# LQFP-QFN-44_Test.net
KiCad netlist of a schematic drawn in EAGLE
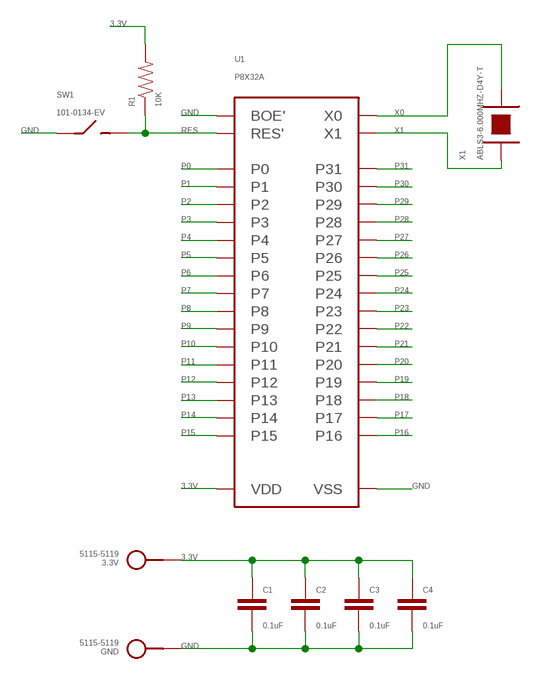
[diagram p0: schematic, sheet 1]

(export (version "E")
  (design (tool "Eeschema 10.0.6"))
  (components
    (comp (ref "3.3V")
      (value "5115-5119")
      (footprint "eagle-import:KEYSTONE_5115-5119")
      (libsource (lib "eagle-import") (part "TEST_POINT_SINGLEKEYSTONE_5115-5119"))
    )
    (comp (ref "C1")
      (value "0.1uF")
      (footprint "eagle-import:0402")
      (libsource (lib "eagle-import") (part "CAPACITOR_NON_POLAR0402"))
    )
    (comp (ref "C2")
      (value "0.1uF")
      (footprint "eagle-import:0402")
      (libsource (lib "eagle-import") (part "CAPACITOR_NON_POLAR0402"))
    )
    (comp (ref "C3")
      (value "0.1uF")
      (footprint "eagle-import:0402")
      (libsource (lib "eagle-import") (part "CAPACITOR_NON_POLAR0402"))
    )
    (comp (ref "C4")
      (value "0.1uF")
      (footprint "eagle-import:0402")
      (libsource (lib "eagle-import") (part "CAPACITOR_NON_POLAR0402"))
    )
    (comp (ref "GND")
      (value "5115-5119")
      (footprint "eagle-import:KEYSTONE_5115-5119")
      (libsource (lib "eagle-import") (part "TEST_POINT_SINGLEKEYSTONE_5115-5119"))
    )
    (comp (ref "R1")
      (value "10K")
      (footprint "eagle-import:0402")
      (libsource (lib "eagle-import") (part "RESISTOR0402"))
    )
    (comp (ref "SW1")
      (value "101-0134-EV")
      (footprint "eagle-import:101-0134-EV")
      (libsource (lib "eagle-import") (part "SPST101-0134-EV"))
    )
    (comp (ref "U1")
      (value "P8X32A")
      (footprint "eagle-import:DUAL_LQFP_QFN_44")
      (libsource (lib "eagle-import") (part "P8X32A_PROPELLERLQFP/QFN-44"))
    )
    (comp (ref "X1")
      (value "ABLS3-6.000MHZ-D4Y-T")
      (footprint "eagle-import:HC-49_US_SM")
      (libsource (lib "eagle-import") (part "CRYSTALHC-49"))
    )
  )
  (nets
    (net (code "1") (name "/3.3V") (class "Default")
      (node (ref "3.3V") (pin "P$1") (pinfunction "P$1_P$1") (pintype "bidirectional"))
      (node (ref "C1") (pin "1") (pinfunction "1_1") (pintype "passive"))
      (node (ref "C2") (pin "1") (pinfunction "1_1") (pintype "passive"))
      (node (ref "C3") (pin "1") (pinfunction "1_1") (pintype "passive"))
      (node (ref "C4") (pin "1") (pinfunction "1_1") (pintype "passive"))
      (node (ref "R1") (pin "2") (pinfunction "2_2") (pintype "passive"))
      (node (ref "U1") (pin "18") (pinfunction "VDD_18") (pintype "bidirectional"))
      (node (ref "U1") (pin "30") (pinfunction "VDD_30") (pintype "bidirectional"))
      (node (ref "U1") (pin "40") (pinfunction "VDD_40") (pintype "bidirectional"))
      (node (ref "U1") (pin "52") (pinfunction "VDD_52") (pintype "bidirectional"))
      (node (ref "U1") (pin "62") (pinfunction "VDD_62") (pintype "bidirectional"))
      (node (ref "U1") (pin "74") (pinfunction "VDD_74") (pintype "bidirectional"))
      (node (ref "U1") (pin "8") (pinfunction "VDD_8") (pintype "bidirectional"))
      (node (ref "U1") (pin "84") (pinfunction "VDD_84") (pintype "bidirectional"))
    )
    (net (code "2") (name "/GND") (class "Default")
      (node (ref "C1") (pin "2") (pinfunction "2_2") (pintype "passive"))
      (node (ref "C2") (pin "2") (pinfunction "2_2") (pintype "passive"))
      (node (ref "C3") (pin "2") (pinfunction "2_2") (pintype "passive"))
      (node (ref "C4") (pin "2") (pinfunction "2_2") (pintype "passive"))
      (node (ref "GND") (pin "P$1") (pinfunction "P$1_P$1") (pintype "bidirectional"))
      (node (ref "SW1") (pin "1") (pinfunction "A_1") (pintype "bidirectional"))
      (node (ref "U1") (pin "17") (pinfunction "VSS_17") (pintype "bidirectional"))
      (node (ref "U1") (pin "27") (pinfunction "VSS_27") (pintype "bidirectional"))
      (node (ref "U1") (pin "39") (pinfunction "VSS_39") (pintype "bidirectional"))
      (node (ref "U1") (pin "49") (pinfunction "VSS_49") (pintype "bidirectional"))
      (node (ref "U1") (pin "5") (pinfunction "VSS_5") (pintype "bidirectional"))
      (node (ref "U1") (pin "50") (pinfunction "BOE'_50") (pintype "bidirectional"))
      (node (ref "U1") (pin "6") (pinfunction "BOE'_6") (pintype "bidirectional"))
      (node (ref "U1") (pin "61") (pinfunction "VSS_61") (pintype "bidirectional"))
      (node (ref "U1") (pin "71") (pinfunction "VSS_71") (pintype "bidirectional"))
      (node (ref "U1") (pin "83") (pinfunction "VSS_83") (pintype "bidirectional"))
      (node (ref "U1") (pin "PAD") (pinfunction "VSS_PAD") (pintype "bidirectional"))
    )
    (net (code "3") (name "/P0") (class "Default")
      (node (ref "U1") (pin "41") (pinfunction "P0_41") (pintype "bidirectional"))
      (node (ref "U1") (pin "85") (pinfunction "P0_85") (pintype "bidirectional"))
    )
    (net (code "4") (name "/P1") (class "Default")
      (node (ref "U1") (pin "42") (pinfunction "P1_42") (pintype "bidirectional"))
      (node (ref "U1") (pin "86") (pinfunction "P1_86") (pintype "bidirectional"))
    )
    (net (code "5") (name "/P2") (class "Default")
      (node (ref "U1") (pin "43") (pinfunction "P2_43") (pintype "bidirectional"))
      (node (ref "U1") (pin "87") (pinfunction "P2_87") (pintype "bidirectional"))
    )
    (net (code "6") (name "/P3") (class "Default")
      (node (ref "U1") (pin "44") (pinfunction "P3_44") (pintype "bidirectional"))
      (node (ref "U1") (pin "88") (pinfunction "P3_88") (pintype "bidirectional"))
    )
    (net (code "7") (name "/P4") (class "Default")
      (node (ref "U1") (pin "1") (pinfunction "P4_1") (pintype "bidirectional"))
      (node (ref "U1") (pin "45") (pinfunction "P4_45") (pintype "bidirectional"))
    )
    (net (code "8") (name "/P5") (class "Default")
      (node (ref "U1") (pin "2") (pinfunction "P5_2") (pintype "bidirectional"))
      (node (ref "U1") (pin "46") (pinfunction "P5_46") (pintype "bidirectional"))
    )
    (net (code "9") (name "/P6") (class "Default")
      (node (ref "U1") (pin "3") (pinfunction "P6_3") (pintype "bidirectional"))
      (node (ref "U1") (pin "47") (pinfunction "P6_47") (pintype "bidirectional"))
    )
    (net (code "10") (name "/P7") (class "Default")
      (node (ref "U1") (pin "4") (pinfunction "P7_4") (pintype "bidirectional"))
      (node (ref "U1") (pin "48") (pinfunction "P7_48") (pintype "bidirectional"))
    )
    (net (code "11") (name "/P8") (class "Default")
      (node (ref "U1") (pin "53") (pinfunction "P8_53") (pintype "bidirectional"))
      (node (ref "U1") (pin "9") (pinfunction "P8_9") (pintype "bidirectional"))
    )
    (net (code "12") (name "/P9") (class "Default")
      (node (ref "U1") (pin "10") (pinfunction "P9_10") (pintype "bidirectional"))
      (node (ref "U1") (pin "54") (pinfunction "P9_54") (pintype "bidirectional"))
    )
    (net (code "13") (name "/P10") (class "Default")
      (node (ref "U1") (pin "11") (pinfunction "P10_11") (pintype "bidirectional"))
      (node (ref "U1") (pin "55") (pinfunction "P10_55") (pintype "bidirectional"))
    )
    (net (code "14") (name "/P11") (class "Default")
      (node (ref "U1") (pin "12") (pinfunction "P11_12") (pintype "bidirectional"))
      (node (ref "U1") (pin "56") (pinfunction "P11_56") (pintype "bidirectional"))
    )
    (net (code "15") (name "/P12") (class "Default")
      (node (ref "U1") (pin "13") (pinfunction "P12_13") (pintype "bidirectional"))
      (node (ref "U1") (pin "57") (pinfunction "P12_57") (pintype "bidirectional"))
    )
    (net (code "16") (name "/P13") (class "Default")
      (node (ref "U1") (pin "14") (pinfunction "P13_14") (pintype "bidirectional"))
      (node (ref "U1") (pin "58") (pinfunction "P13_58") (pintype "bidirectional"))
    )
    (net (code "17") (name "/P14") (class "Default")
      (node (ref "U1") (pin "15") (pinfunction "P14_15") (pintype "bidirectional"))
      (node (ref "U1") (pin "59") (pinfunction "P14_59") (pintype "bidirectional"))
    )
    (net (code "18") (name "/P15") (class "Default")
      (node (ref "U1") (pin "16") (pinfunction "P15_16") (pintype "bidirectional"))
      (node (ref "U1") (pin "60") (pinfunction "P15_60") (pintype "bidirectional"))
    )
    (net (code "19") (name "/P16") (class "Default")
      (node (ref "U1") (pin "19") (pinfunction "P16_19") (pintype "bidirectional"))
      (node (ref "U1") (pin "63") (pinfunction "P16_63") (pintype "bidirectional"))
    )
    (net (code "20") (name "/P17") (class "Default")
      (node (ref "U1") (pin "20") (pinfunction "P17_20") (pintype "bidirectional"))
      (node (ref "U1") (pin "64") (pinfunction "P17_64") (pintype "bidirectional"))
    )
    (net (code "21") (name "/P18") (class "Default")
      (node (ref "U1") (pin "21") (pinfunction "P18_21") (pintype "bidirectional"))
      (node (ref "U1") (pin "65") (pinfunction "P18_65") (pintype "bidirectional"))
    )
    (net (code "22") (name "/P19") (class "Default")
      (node (ref "U1") (pin "22") (pinfunction "P19_22") (pintype "bidirectional"))
      (node (ref "U1") (pin "66") (pinfunction "P19_66") (pintype "bidirectional"))
    )
    (net (code "23") (name "/P20") (class "Default")
      (node (ref "U1") (pin "23") (pinfunction "P20_23") (pintype "bidirectional"))
      (node (ref "U1") (pin "67") (pinfunction "P20_67") (pintype "bidirectional"))
    )
    (net (code "24") (name "/P21") (class "Default")
      (node (ref "U1") (pin "24") (pinfunction "P21_24") (pintype "bidirectional"))
      (node (ref "U1") (pin "68") (pinfunction "P21_68") (pintype "bidirectional"))
    )
    (net (code "25") (name "/P22") (class "Default")
      (node (ref "U1") (pin "25") (pinfunction "P22_25") (pintype "bidirectional"))
      (node (ref "U1") (pin "69") (pinfunction "P22_69") (pintype "bidirectional"))
    )
    (net (code "26") (name "/P23") (class "Default")
      (node (ref "U1") (pin "26") (pinfunction "P23_26") (pintype "bidirectional"))
      (node (ref "U1") (pin "70") (pinfunction "P23_70") (pintype "bidirectional"))
    )
    (net (code "27") (name "/P24") (class "Default")
      (node (ref "U1") (pin "31") (pinfunction "P24_31") (pintype "bidirectional"))
      (node (ref "U1") (pin "75") (pinfunction "P24_75") (pintype "bidirectional"))
    )
    (net (code "28") (name "/P25") (class "Default")
      (node (ref "U1") (pin "32") (pinfunction "P25_32") (pintype "bidirectional"))
      (node (ref "U1") (pin "76") (pinfunction "P25_76") (pintype "bidirectional"))
    )
    (net (code "29") (name "/P26") (class "Default")
      (node (ref "U1") (pin "33") (pinfunction "P26_33") (pintype "bidirectional"))
      (node (ref "U1") (pin "77") (pinfunction "P26_77") (pintype "bidirectional"))
    )
    (net (code "30") (name "/P27") (class "Default")
      (node (ref "U1") (pin "34") (pinfunction "P27_34") (pintype "bidirectional"))
      (node (ref "U1") (pin "78") (pinfunction "P27_78") (pintype "bidirectional"))
    )
    (net (code "31") (name "/P28") (class "Default")
      (node (ref "U1") (pin "35") (pinfunction "P28_35") (pintype "bidirectional"))
      (node (ref "U1") (pin "79") (pinfunction "P28_79") (pintype "bidirectional"))
    )
    (net (code "32") (name "/P29") (class "Default")
      (node (ref "U1") (pin "36") (pinfunction "P29_36") (pintype "bidirectional"))
      (node (ref "U1") (pin "80") (pinfunction "P29_80") (pintype "bidirectional"))
    )
    (net (code "33") (name "/P30") (class "Default")
      (node (ref "U1") (pin "37") (pinfunction "P30_37") (pintype "bidirectional"))
      (node (ref "U1") (pin "81") (pinfunction "P30_81") (pintype "bidirectional"))
    )
    (net (code "34") (name "/P31") (class "Default")
      (node (ref "U1") (pin "38") (pinfunction "P31_38") (pintype "bidirectional"))
      (node (ref "U1") (pin "82") (pinfunction "P31_82") (pintype "bidirectional"))
    )
    (net (code "35") (name "/RES") (class "Default")
      (node (ref "R1") (pin "1") (pinfunction "1_1") (pintype "passive"))
      (node (ref "SW1") (pin "2") (pinfunction "B_2") (pintype "bidirectional"))
      (node (ref "U1") (pin "51") (pinfunction "RES'_51") (pintype "bidirectional"))
      (node (ref "U1") (pin "7") (pinfunction "RES'_7") (pintype "bidirectional"))
    )
    (net (code "36") (name "/X0") (class "Default")
      (node (ref "U1") (pin "29") (pinfunction "X0_29") (pintype "bidirectional"))
      (node (ref "U1") (pin "73") (pinfunction "X0_73") (pintype "bidirectional"))
      (node (ref "X1") (pin "P$2") (pinfunction "P$2_P$2") (pintype "bidirectional"))
    )
    (net (code "37") (name "/X1") (class "Default")
      (node (ref "U1") (pin "28") (pinfunction "X1_28") (pintype "bidirectional"))
      (node (ref "U1") (pin "72") (pinfunction "X1_72") (pintype "bidirectional"))
      (node (ref "X1") (pin "P$1") (pinfunction "P$1_P$1") (pintype "bidirectional"))
    )
  )
)
